# main.net
KiCad netlist of a schematic drawn in Altium Designer
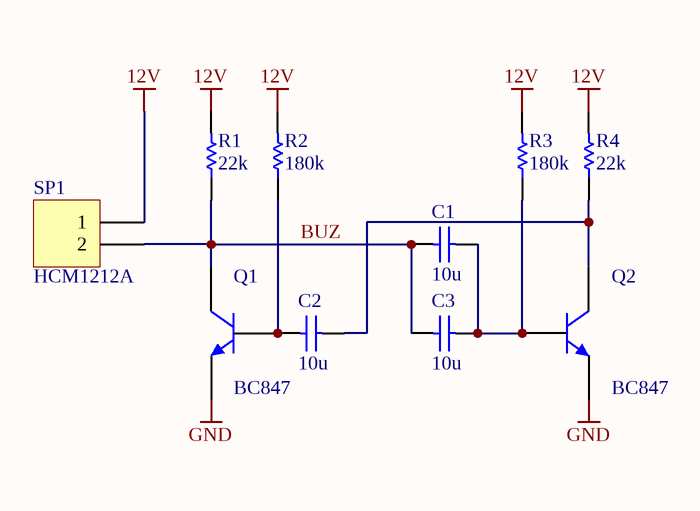
[diagram p0: main.SchDoc]

(export (version "E")
  (design (tool "Eeschema 10.0.6"))
  (components
    (comp (ref "C1")
      (value "10u")
      (footprint "C1210-2.5MM")
      (libsource (lib "Miscellaneous Devices") (part "Cap"))
    )
    (comp (ref "C2")
      (value "10u")
      (footprint "C1210-2.5MM")
      (libsource (lib "Miscellaneous Devices") (part "Cap"))
    )
    (comp (ref "C3")
      (value "10u")
      (footprint "C1210-2.5MM")
      (libsource (lib "Miscellaneous Devices") (part "Cap"))
    )
    (comp (ref "Q1") (value "BC847") (footprint "SOT-23") (libsource (lib "Schlib1") (part "MMBT2222ALT1G")))
    (comp (ref "Q2") (value "BC847") (footprint "SOT-23") (libsource (lib "Schlib1") (part "MMBT2222ALT1G")))
    (comp (ref "R1")
      (value "22k")
      (footprint "R0805")
      (libsource (lib "Miscellaneous Devices") (part "Res1"))
    )
    (comp (ref "R2")
      (value "180k")
      (footprint "R1206")
      (libsource (lib "Miscellaneous Devices") (part "Res1"))
    )
    (comp (ref "R3")
      (value "180k")
      (footprint "R1206")
      (libsource (lib "Miscellaneous Devices") (part "Res1"))
    )
    (comp (ref "R4")
      (value "22k")
      (footprint "R0805")
      (libsource (lib "Miscellaneous Devices") (part "Res1"))
    )
    (comp (ref "SP1")
      (value "HCM1212A")
      (footprint "BUZZER")
      (description "HCM1212X / 12V, 2.3Hz, 85dB/10cm, with gen.")
      (libsource (lib "Schlib1") (part "Header 2"))
    )
  )
  (nets
    (net (code "1") (name "/BUZ") (class "Default")
      (node (ref "C1") (pin "2") (pinfunction "2_2") (pintype "passive"))
      (node (ref "C3") (pin "2") (pinfunction "2_2") (pintype "passive"))
      (node (ref "Q1") (pin "3") (pinfunction "C_3") (pintype "passive"))
      (node (ref "R1") (pin "1") (pinfunction "1_1") (pintype "passive"))
      (node (ref "SP1") (pin "2") (pinfunction "2_2") (pintype "passive"))
    )
    (net (code "2") (name "12V") (class "Default")
      (node (ref "R1") (pin "2") (pinfunction "2_2") (pintype "passive"))
      (node (ref "R2") (pin "2") (pinfunction "2_2") (pintype "passive"))
      (node (ref "R3") (pin "2") (pinfunction "2_2") (pintype "passive"))
      (node (ref "R4") (pin "2") (pinfunction "2_2") (pintype "passive"))
      (node (ref "SP1") (pin "1") (pinfunction "1_1") (pintype "passive"))
    )
    (net (code "3") (name "GND") (class "Default")
      (node (ref "Q1") (pin "2") (pinfunction "E_2") (pintype "passive"))
      (node (ref "Q2") (pin "2") (pinfunction "E_2") (pintype "passive"))
    )
    (net (code "4") (name "Net-(Q1-B)") (class "Default")
      (node (ref "C2") (pin "2") (pinfunction "2_2") (pintype "passive"))
      (node (ref "Q1") (pin "1") (pinfunction "B_1") (pintype "passive"))
      (node (ref "R2") (pin "1") (pinfunction "1_1") (pintype "passive"))
    )
    (net (code "5") (name "Net-(Q2-B)") (class "Default")
      (node (ref "C1") (pin "1") (pinfunction "1_1") (pintype "passive"))
      (node (ref "C3") (pin "1") (pinfunction "1_1") (pintype "passive"))
      (node (ref "Q2") (pin "1") (pinfunction "B_1") (pintype "passive"))
      (node (ref "R3") (pin "1") (pinfunction "1_1") (pintype "passive"))
    )
    (net (code "6") (name "Net-(Q2-C)") (class "Default")
      (node (ref "C2") (pin "1") (pinfunction "1_1") (pintype "passive"))
      (node (ref "Q2") (pin "3") (pinfunction "C_3") (pintype "passive"))
      (node (ref "R4") (pin "1") (pinfunction "1_1") (pintype "passive"))
    )
  )
)
